# GPIO_OUT.net
KiCad netlist of a schematic drawn in Altium Designer
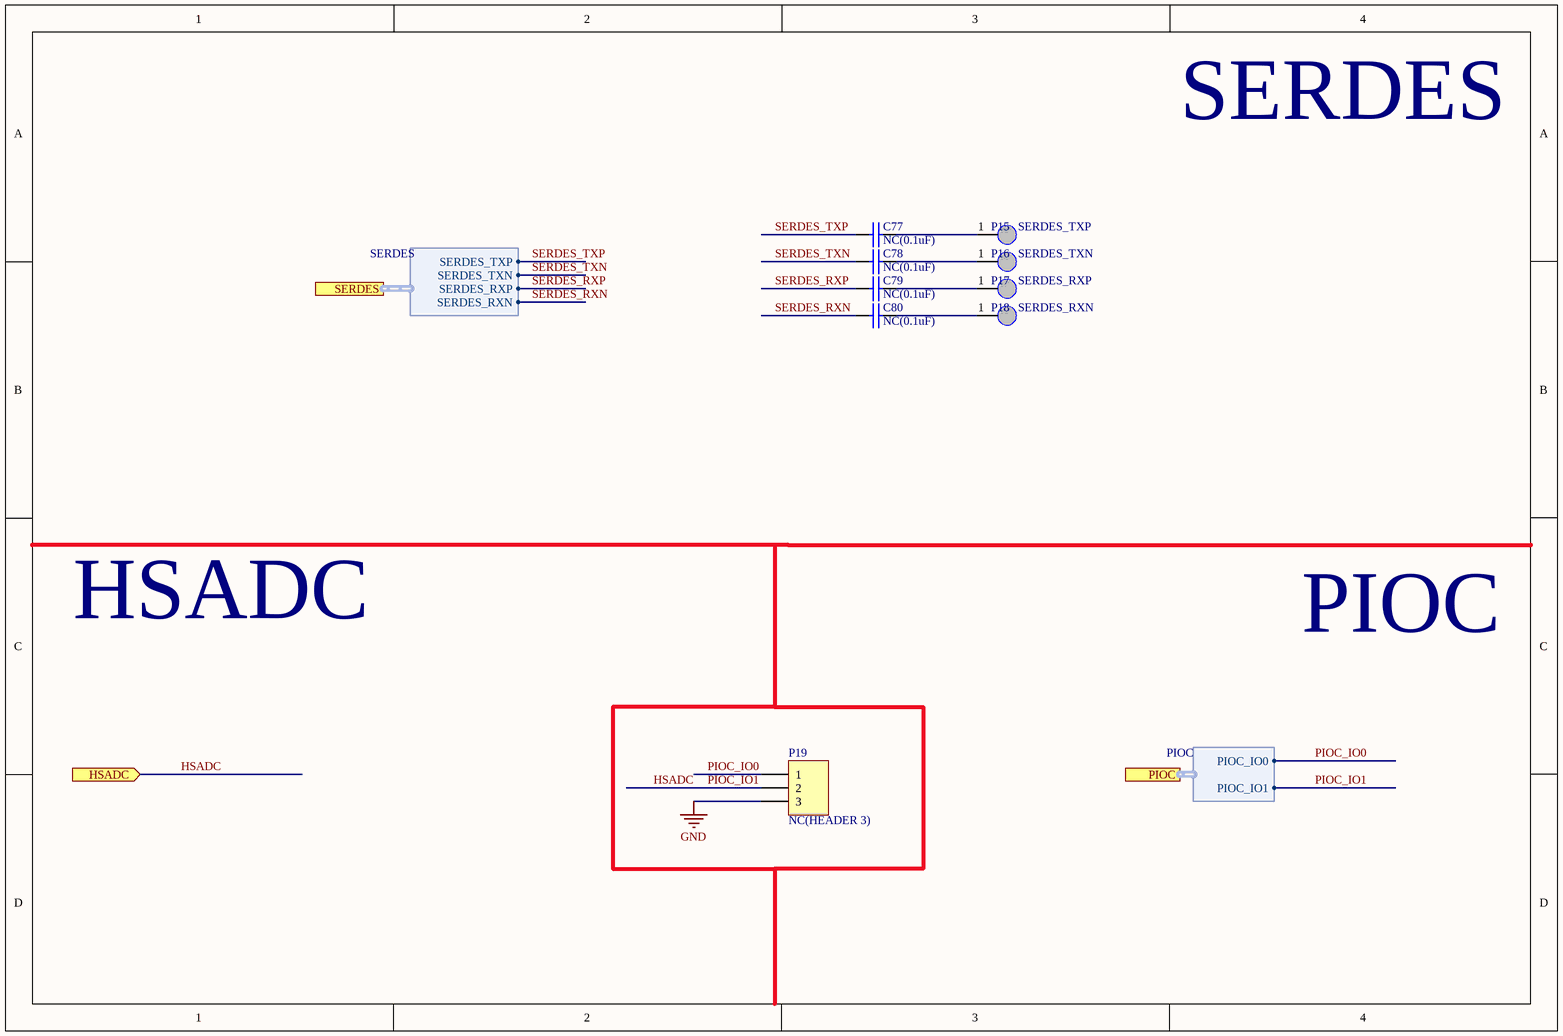
[diagram p0: GPIO_OUT.SchDoc]

(export (version "E")
  (design (tool "Eeschema 10.0.6"))
  (components
    (comp (ref "C77")
      (value "NC(0.1uF)")
      (footprint "0402_C")
      (description "Capacitor")
      (libsource (lib "*") (part "CAP"))
    )
    (comp (ref "C78")
      (value "NC(0.1uF)")
      (footprint "0402_C")
      (description "Capacitor")
      (libsource (lib "*") (part "CAP"))
    )
    (comp (ref "C79")
      (value "NC(0.1uF)")
      (footprint "0402_C")
      (description "Capacitor")
      (libsource (lib "*") (part "CAP"))
    )
    (comp (ref "C80")
      (value "NC(0.1uF)")
      (footprint "0402_C")
      (description "Capacitor")
      (libsource (lib "*") (part "CAP"))
    )
    (comp (ref "P15")
      (value "SERDES_TXP")
      (footprint "TESTPOINT1")
      (description "焊盘")
      (libsource (lib "wch_sch_others") (part "PAD"))
    )
    (comp (ref "P16")
      (value "SERDES_TXN")
      (footprint "TESTPOINT1")
      (description "焊盘")
      (libsource (lib "wch_sch_others") (part "PAD"))
    )
    (comp (ref "P17")
      (value "SERDES_RXP")
      (footprint "TESTPOINT1")
      (description "焊盘")
      (libsource (lib "wch_sch_others") (part "PAD"))
    )
    (comp (ref "P18")
      (value "SERDES_RXN")
      (footprint "TESTPOINT1")
      (description "焊盘")
      (libsource (lib "wch_sch_others") (part "PAD"))
    )
    (comp (ref "P19")
      (value "NC(HEADER 3)")
      (footprint "SIP3-2.54MM")
      (description "Header, 3-Pin")
      (libsource (lib "wch_sch_others") (part "HEADER 3"))
    )
  )
  (nets
    (net (code "3") (name "/HSADC") (class "Default")
      (node (ref "P19") (pin "2") (pinfunction "2_2") (pintype "passive"))
    )
    (net (code "4") (name "/PIOC_IO0") (class "Default")
      (node (ref "P19") (pin "1") (pinfunction "1_1") (pintype "passive"))
    )
    (net (code "5") (name "/SERDES_RXN") (class "Default")
      (node (ref "C80") (pin "1") (pinfunction "1_1") (pintype "passive"))
    )
    (net (code "6") (name "/SERDES_RXP") (class "Default")
      (node (ref "C79") (pin "1") (pinfunction "1_1") (pintype "passive"))
    )
    (net (code "7") (name "/SERDES_TXN") (class "Default")
      (node (ref "C78") (pin "1") (pinfunction "1_1") (pintype "passive"))
    )
    (net (code "8") (name "/SERDES_TXP") (class "Default")
      (node (ref "C77") (pin "1") (pinfunction "1_1") (pintype "passive"))
    )
    (net (code "11") (name "GND") (class "Default")
      (node (ref "P19") (pin "3") (pinfunction "3_3") (pintype "passive"))
    )
    (net (code "12") (name "Net-(C77-Pad2)") (class "Default")
      (node (ref "C77") (pin "2") (pinfunction "2_2") (pintype "passive"))
      (node (ref "P15") (pin "1") (pintype "passive"))
    )
    (net (code "13") (name "Net-(C78-Pad2)") (class "Default")
      (node (ref "C78") (pin "2") (pinfunction "2_2") (pintype "passive"))
      (node (ref "P16") (pin "1") (pintype "passive"))
    )
    (net (code "14") (name "Net-(C79-Pad2)") (class "Default")
      (node (ref "C79") (pin "2") (pinfunction "2_2") (pintype "passive"))
      (node (ref "P17") (pin "1") (pintype "passive"))
    )
    (net (code "15") (name "Net-(C80-Pad2)") (class "Default")
      (node (ref "C80") (pin "2") (pinfunction "2_2") (pintype "passive"))
      (node (ref "P18") (pin "1") (pintype "passive"))
    )
  )
)
